# dummyLoad.net
KiCad netlist of a schematic drawn in EAGLE
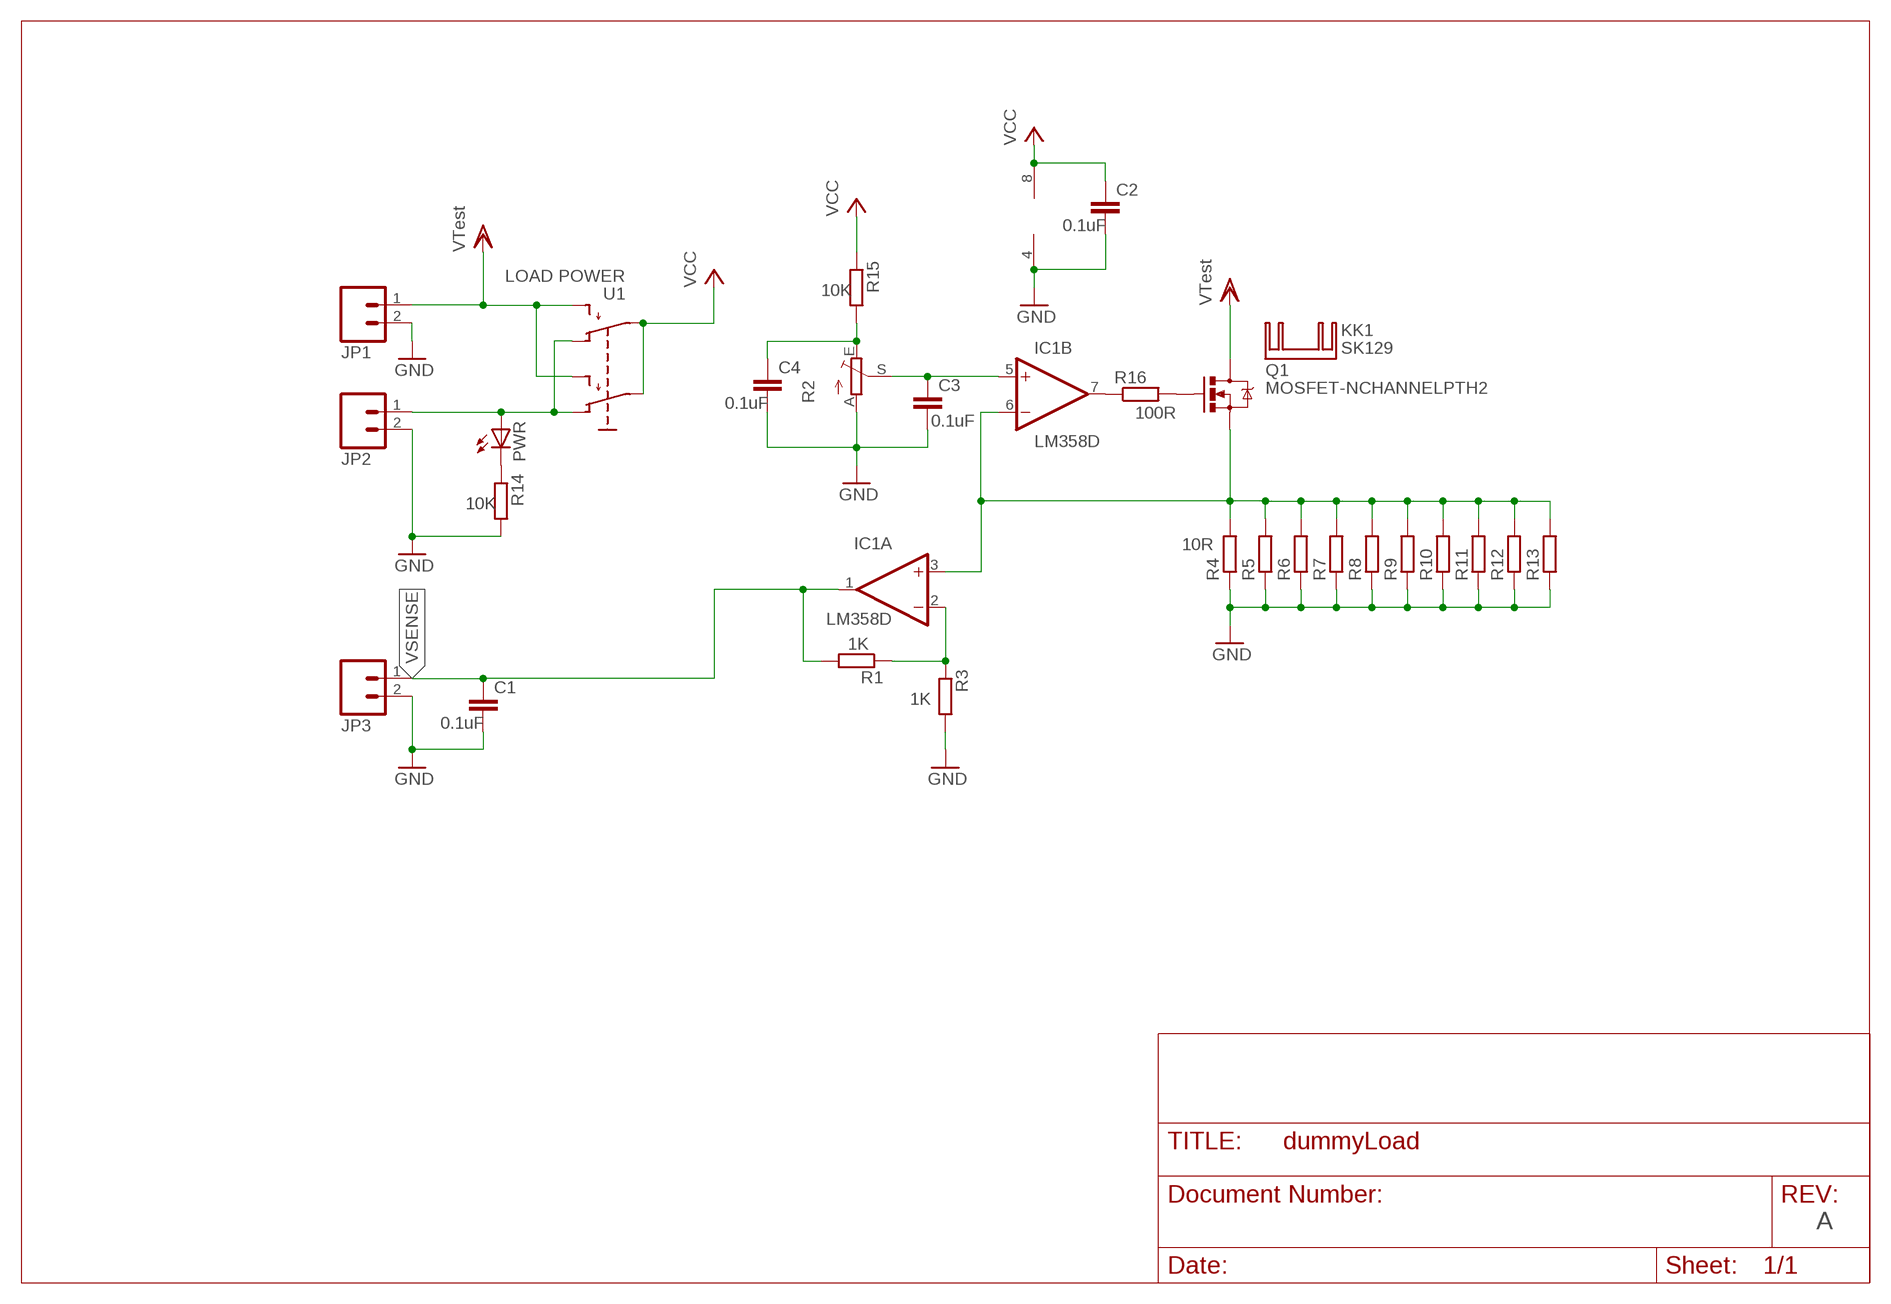
[diagram p0: schematic, sheet 1]

(export (version "E")
  (design (tool "Eeschema 10.0.6"))
  (components
    (comp (ref "C1")
      (value "0.1uF")
      (footprint "eagle-import:C0805")
      (libsource (lib "eagle-import") (part "C-EUC0805"))
    )
    (comp (ref "C2")
      (value "0.1uF")
      (footprint "eagle-import:C0805")
      (libsource (lib "eagle-import") (part "C-EUC0805"))
    )
    (comp (ref "C3")
      (value "0.1uF")
      (footprint "eagle-import:C0805")
      (libsource (lib "eagle-import") (part "C-EUC0805"))
    )
    (comp (ref "C4")
      (value "0.1uF")
      (footprint "eagle-import:C0805")
      (libsource (lib "eagle-import") (part "C-EUC0805"))
    )
    (comp (ref "IC1")
      (value "LM358D")
      (footprint "eagle-import:SO08")
      (libsource (lib "eagle-import") (part "LM358D"))
    )
    (comp (ref "JP1")
      (value "M02PTH")
      (footprint "eagle-import:1X02")
      (libsource (lib "eagle-import") (part "M02PTH"))
    )
    (comp (ref "JP2")
      (value "M02PTH")
      (footprint "eagle-import:1X02")
      (libsource (lib "eagle-import") (part "M02PTH"))
    )
    (comp (ref "JP3")
      (value "M02PTH")
      (footprint "eagle-import:1X02")
      (libsource (lib "eagle-import") (part "M02PTH"))
    )
    (comp (ref "KK1")
      (value "SK129")
      (footprint "eagle-import:SK129-HOLE")
      (libsource (lib "eagle-import") (part "SK129"))
    )
    (comp (ref "PWR")
      (value "LEDCHIPLED_0805")
      (footprint "eagle-import:CHIPLED_0805")
      (libsource (lib "eagle-import") (part "LEDCHIPLED_0805"))
    )
    (comp (ref "Q1")
      (value "MOSFET-NCHANNELPTH2")
      (footprint "eagle-import:TO220V")
      (libsource (lib "eagle-import") (part "MOSFET-NCHANNELPTH2"))
    )
    (comp (ref "R1")
      (value "1K")
      (footprint "eagle-import:M0805")
      (libsource (lib "eagle-import") (part "R-EU_M0805"))
    )
    (comp (ref "R2")
      (value "TRIM_EU-B64Y")
      (footprint "eagle-import:B64Y")
      (libsource (lib "eagle-import") (part "TRIM_EU-B64Y"))
    )
    (comp (ref "R3")
      (value "1K")
      (footprint "eagle-import:M0805")
      (libsource (lib "eagle-import") (part "R-EU_M0805"))
    )
    (comp (ref "R4")
      (value "10R")
      (footprint "eagle-import:M0805")
      (libsource (lib "eagle-import") (part "R-EU_M0805"))
    )
    (comp (ref "R5")
      (value "R-EU_M0805")
      (footprint "eagle-import:M0805")
      (libsource (lib "eagle-import") (part "R-EU_M0805"))
    )
    (comp (ref "R6")
      (value "R-EU_M0805")
      (footprint "eagle-import:M0805")
      (libsource (lib "eagle-import") (part "R-EU_M0805"))
    )
    (comp (ref "R7")
      (value "R-EU_M0805")
      (footprint "eagle-import:M0805")
      (libsource (lib "eagle-import") (part "R-EU_M0805"))
    )
    (comp (ref "R8")
      (value "R-EU_M0805")
      (footprint "eagle-import:M0805")
      (libsource (lib "eagle-import") (part "R-EU_M0805"))
    )
    (comp (ref "R9")
      (value "R-EU_M0805")
      (footprint "eagle-import:M0805")
      (libsource (lib "eagle-import") (part "R-EU_M0805"))
    )
    (comp (ref "R10")
      (value "R-EU_M0805")
      (footprint "eagle-import:M0805")
      (libsource (lib "eagle-import") (part "R-EU_M0805"))
    )
    (comp (ref "R11")
      (value "R-EU_M0805")
      (footprint "eagle-import:M0805")
      (libsource (lib "eagle-import") (part "R-EU_M0805"))
    )
    (comp (ref "R12")
      (value "R-EU_M0805")
      (footprint "eagle-import:M0805")
      (libsource (lib "eagle-import") (part "R-EU_M0805"))
    )
    (comp (ref "R13")
      (value "R-EU_M0805")
      (footprint "eagle-import:M0805")
      (libsource (lib "eagle-import") (part "R-EU_M0805"))
    )
    (comp (ref "R14")
      (value "10K")
      (footprint "eagle-import:M0805")
      (libsource (lib "eagle-import") (part "R-EU_M0805"))
    )
    (comp (ref "R15")
      (value "10K")
      (footprint "eagle-import:M0805")
      (libsource (lib "eagle-import") (part "R-EU_M0805"))
    )
    (comp (ref "R16")
      (value "100R")
      (footprint "eagle-import:M0805")
      (libsource (lib "eagle-import") (part "R-EU_M0805"))
    )
    (comp (ref "U1")
      (value "LOAD POWER")
      (footprint "eagle-import:SWITCH-JS202011")
      (libsource (lib "eagle-import") (part "MINI_SWITCH"))
    )
  )
  (nets
    (net (code "1") (name "GND") (class "Default")
      (node (ref "C1") (pin "2") (pinfunction "2_2") (pintype "passive"))
      (node (ref "C2") (pin "2") (pinfunction "2_2") (pintype "passive"))
      (node (ref "C3") (pin "2") (pinfunction "2_2") (pintype "passive"))
      (node (ref "C4") (pin "2") (pinfunction "2_2") (pintype "passive"))
      (node (ref "IC1") (pin "4") (pinfunction "V-_4") (pintype "power_in"))
      (node (ref "JP1") (pin "2") (pinfunction "2_2") (pintype "passive"))
      (node (ref "JP2") (pin "2") (pinfunction "2_2") (pintype "passive"))
      (node (ref "JP3") (pin "2") (pinfunction "2_2") (pintype "passive"))
      (node (ref "R10") (pin "1") (pinfunction "1_1") (pintype "passive"))
      (node (ref "R11") (pin "1") (pinfunction "1_1") (pintype "passive"))
      (node (ref "R12") (pin "1") (pinfunction "1_1") (pintype "passive"))
      (node (ref "R13") (pin "1") (pinfunction "1_1") (pintype "passive"))
      (node (ref "R14") (pin "2") (pinfunction "2_2") (pintype "passive"))
      (node (ref "R2") (pin "A") (pinfunction "A_A") (pintype "passive"))
      (node (ref "R3") (pin "2") (pinfunction "2_2") (pintype "passive"))
      (node (ref "R4") (pin "1") (pinfunction "1_1") (pintype "passive"))
      (node (ref "R5") (pin "1") (pinfunction "1_1") (pintype "passive"))
      (node (ref "R6") (pin "1") (pinfunction "1_1") (pintype "passive"))
      (node (ref "R7") (pin "1") (pinfunction "1_1") (pintype "passive"))
      (node (ref "R8") (pin "1") (pinfunction "1_1") (pintype "passive"))
      (node (ref "R9") (pin "1") (pinfunction "1_1") (pintype "passive"))
    )
    (net (code "2") (name "Net-(C4-Pad1)") (class "Default")
      (node (ref "C4") (pin "1") (pinfunction "1_1") (pintype "passive"))
      (node (ref "R15") (pin "2") (pinfunction "2_2") (pintype "passive"))
      (node (ref "R2") (pin "E") (pinfunction "E_E") (pintype "passive"))
    )
    (net (code "3") (name "Net-(IC1A-+IN)") (class "Default")
      (node (ref "IC1") (pin "3") (pinfunction "+IN_3") (pintype "input"))
      (node (ref "IC1") (pin "6") (pinfunction "-IN_6") (pintype "input"))
      (node (ref "Q1") (pin "3") (pinfunction "S_3") (pintype "passive"))
      (node (ref "R10") (pin "2") (pinfunction "2_2") (pintype "passive"))
      (node (ref "R11") (pin "2") (pinfunction "2_2") (pintype "passive"))
      (node (ref "R12") (pin "2") (pinfunction "2_2") (pintype "passive"))
      (node (ref "R13") (pin "2") (pinfunction "2_2") (pintype "passive"))
      (node (ref "R4") (pin "2") (pinfunction "2_2") (pintype "passive"))
      (node (ref "R5") (pin "2") (pinfunction "2_2") (pintype "passive"))
      (node (ref "R6") (pin "2") (pinfunction "2_2") (pintype "passive"))
      (node (ref "R7") (pin "2") (pinfunction "2_2") (pintype "passive"))
      (node (ref "R8") (pin "2") (pinfunction "2_2") (pintype "passive"))
      (node (ref "R9") (pin "2") (pinfunction "2_2") (pintype "passive"))
    )
    (net (code "4") (name "Net-(IC1A--IN)") (class "Default")
      (node (ref "IC1") (pin "2") (pinfunction "-IN_2") (pintype "input"))
      (node (ref "R1") (pin "1") (pinfunction "1_1") (pintype "passive"))
      (node (ref "R3") (pin "1") (pinfunction "1_1") (pintype "passive"))
    )
    (net (code "5") (name "Net-(IC1B-+IN)") (class "Default")
      (node (ref "C3") (pin "1") (pinfunction "1_1") (pintype "passive"))
      (node (ref "IC1") (pin "5") (pinfunction "+IN_5") (pintype "input"))
      (node (ref "R2") (pin "S") (pinfunction "S_S") (pintype "passive"))
    )
    (net (code "6") (name "Net-(IC1B-OUT)") (class "Default")
      (node (ref "IC1") (pin "7") (pinfunction "OUT_7") (pintype "output"))
      (node (ref "R16") (pin "1") (pinfunction "1_1") (pintype "passive"))
    )
    (net (code "7") (name "Net-(PWR-PadC)") (class "Default")
      (node (ref "PWR") (pin "C") (pinfunction "C_C") (pintype "passive"))
      (node (ref "R14") (pin "1") (pinfunction "1_1") (pintype "passive"))
    )
    (net (code "8") (name "Net-(Q1-G)") (class "Default")
      (node (ref "Q1") (pin "1") (pinfunction "G_1") (pintype "passive"))
      (node (ref "R16") (pin "2") (pinfunction "2_2") (pintype "passive"))
    )
    (net (code "9") (name "Net-(U1-O)") (class "Default")
      (node (ref "JP2") (pin "1") (pinfunction "1_1") (pintype "passive"))
      (node (ref "PWR") (pin "A") (pinfunction "A_A") (pintype "passive"))
      (node (ref "U1") (pin "P1") (pinfunction "O_P1") (pintype "passive"))
      (node (ref "U1") (pin "P4") (pinfunction "O1_P4") (pintype "passive"))
    )
    (net (code "10") (name "VCC") (class "Default")
      (node (ref "C2") (pin "1") (pinfunction "1_1") (pintype "passive"))
      (node (ref "IC1") (pin "8") (pinfunction "V+_8") (pintype "power_in"))
      (node (ref "R15") (pin "1") (pinfunction "1_1") (pintype "passive"))
      (node (ref "U1") (pin "P2") (pinfunction "P_P2") (pintype "passive"))
      (node (ref "U1") (pin "P5") (pinfunction "P1_P5") (pintype "passive"))
    )
    (net (code "11") (name "VSENSE") (class "Default")
      (node (ref "C1") (pin "1") (pinfunction "1_1") (pintype "passive"))
      (node (ref "IC1") (pin "1") (pinfunction "OUT_1") (pintype "output"))
      (node (ref "JP3") (pin "1") (pinfunction "1_1") (pintype "passive"))
      (node (ref "R1") (pin "2") (pinfunction "2_2") (pintype "passive"))
    )
    (net (code "12") (name "VTest") (class "Default")
      (node (ref "JP1") (pin "1") (pinfunction "1_1") (pintype "passive"))
      (node (ref "Q1") (pin "2") (pinfunction "D_2") (pintype "passive"))
      (node (ref "U1") (pin "P3") (pinfunction "S_P3") (pintype "passive"))
      (node (ref "U1") (pin "P6") (pinfunction "S1_P6") (pintype "passive"))
    )
  )
)
